# Controller.net
KiCad netlist of a schematic drawn in EAGLE
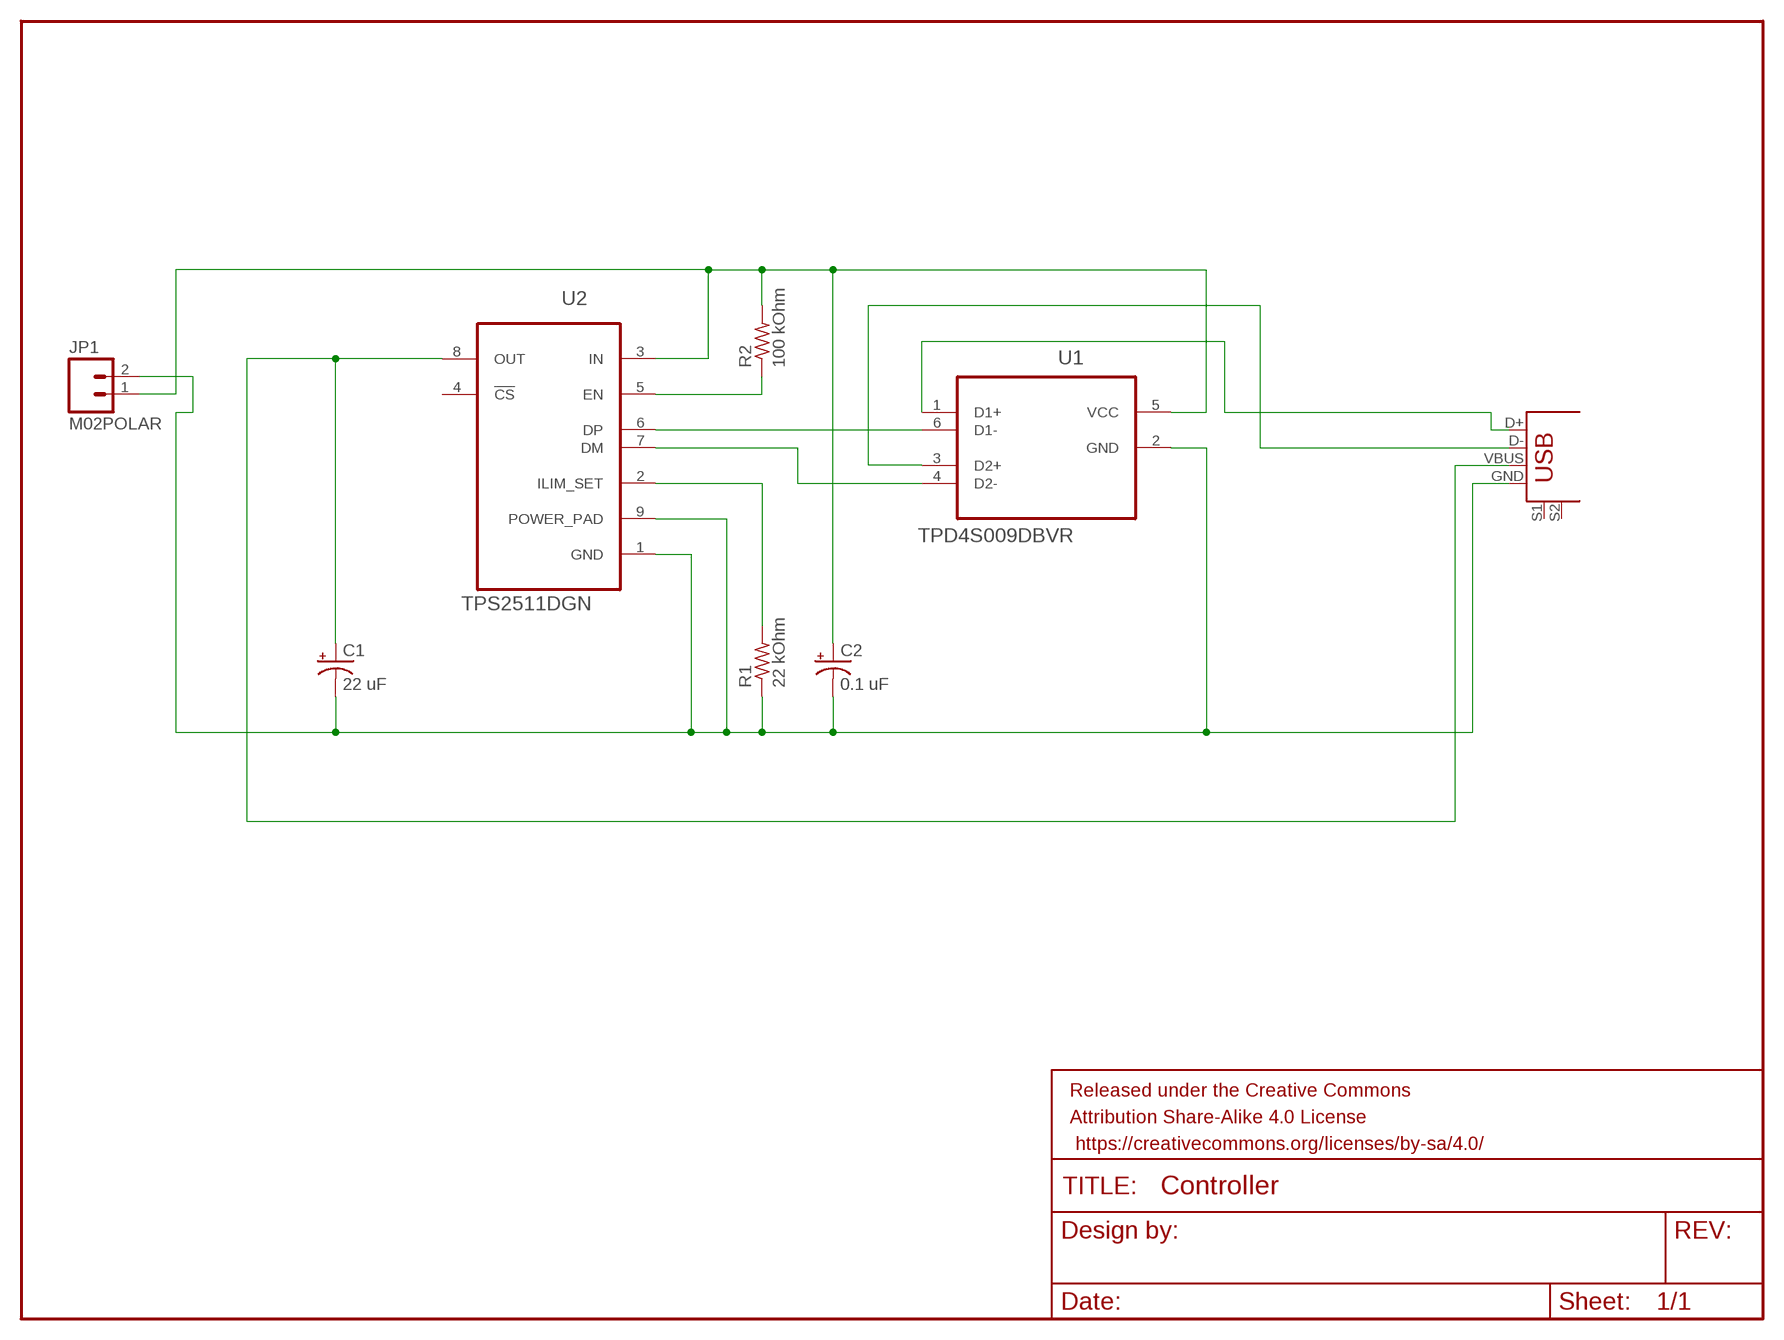
[diagram p0: schematic, sheet 1]

(export (version "E")
  (design (tool "Eeschema 10.0.6"))
  (components
    (comp (ref "C1")
      (value "22 uF")
      (footprint "eagle-import:E2,5-5")
      (libsource (lib "eagle-import") (part "CPOL-USE2.5-5"))
    )
    (comp (ref "C2")
      (value "0.1 uF")
      (footprint "eagle-import:E2,5-5")
      (libsource (lib "eagle-import") (part "CPOL-USE2.5-5"))
    )
    (comp (ref "FRAME1")
      (value "FRAME-LETTER")
      (footprint "eagle-import:CREATIVE_COMMONS")
      (libsource (lib "eagle-import") (part "FRAME-LETTER"))
    )
    (comp (ref "JP1")
      (value "M02POLAR")
      (footprint "eagle-import:MOLEX-1X2")
      (libsource (lib "eagle-import") (part "M02POLAR"))
    )
    (comp (ref "R1")
      (value "22 kOhm")
      (footprint "eagle-import:0207_10")
      (libsource (lib "eagle-import") (part "R-US_0207/10"))
    )
    (comp (ref "R2")
      (value "100 kOhm")
      (footprint "eagle-import:0207_10")
      (libsource (lib "eagle-import") (part "R-US_0207/10"))
    )
    (comp (ref "U$2")
      (value "USB+SHIELDUSB-A-S-NOSILK-FEMALE")
      (footprint "eagle-import:USB-A-S-NOSILK-FEMALE")
      (libsource (lib "eagle-import") (part "USB+SHIELDUSB-A-S-NOSILK-FEMALE"))
    )
    (comp (ref "U1")
      (value "TPD4S009DBVR")
      (footprint "eagle-import:SOT95P280X145-6N")
      (libsource (lib "eagle-import") (part "TPD4S009DBVR"))
    )
    (comp (ref "U2")
      (value "TPS2511DGN")
      (footprint "eagle-import:SOP65P490X110-9N")
      (fields (field (name "MPN") "TPS2511DGN "))
      (libsource (lib "eagle-import") (part "TPS2511DGN"))
    )
  )
  (nets
    (net (code "1") (name "Net-(U1-D1+)") (class "Default")
      (node (ref "U$2") (pin "D+") (pinfunction "D+_D+") (pintype "bidirectional"))
      (node (ref "U1") (pin "1") (pinfunction "D1+_1") (pintype "input"))
    )
    (net (code "2") (name "Net-(U1-D1-)") (class "Default")
      (node (ref "U1") (pin "6") (pinfunction "D1-_6") (pintype "input"))
      (node (ref "U2") (pin "6") (pinfunction "DP_6") (pintype "bidirectional"))
    )
    (net (code "3") (name "Net-(U1-D2+)") (class "Default")
      (node (ref "U$2") (pin "D-") (pinfunction "D-_D-") (pintype "bidirectional"))
      (node (ref "U1") (pin "3") (pinfunction "D2+_3") (pintype "input"))
    )
    (net (code "4") (name "Net-(U1-D2-)") (class "Default")
      (node (ref "U1") (pin "4") (pinfunction "D2-_4") (pintype "input"))
      (node (ref "U2") (pin "7") (pinfunction "DM_7") (pintype "bidirectional"))
    )
    (net (code "5") (name "Net-(U1-GND)") (class "Default")
      (node (ref "C1") (pin "-") (pinfunction "-_-") (pintype "passive"))
      (node (ref "C2") (pin "-") (pinfunction "-_-") (pintype "passive"))
      (node (ref "JP1") (pin "2") (pinfunction "2_2") (pintype "passive"))
      (node (ref "R1") (pin "1") (pinfunction "1_1") (pintype "passive"))
      (node (ref "U$2") (pin "GND") (pinfunction "GND_GND") (pintype "bidirectional"))
      (node (ref "U1") (pin "2") (pinfunction "GND_2") (pintype "passive"))
      (node (ref "U2") (pin "1") (pinfunction "GND_1") (pintype "passive"))
      (node (ref "U2") (pin "9") (pinfunction "POWER_PAD_9") (pintype "passive"))
    )
    (net (code "6") (name "Net-(U1-VCC)") (class "Default")
      (node (ref "C2") (pin "+") (pinfunction "+_+") (pintype "passive"))
      (node (ref "JP1") (pin "1") (pinfunction "1_1") (pintype "passive"))
      (node (ref "R2") (pin "2") (pinfunction "2_2") (pintype "passive"))
      (node (ref "U1") (pin "5") (pinfunction "VCC_5") (pintype "power_in"))
      (node (ref "U2") (pin "3") (pinfunction "IN_3") (pintype "power_in"))
    )
    (net (code "7") (name "Net-(U2-EN)") (class "Default")
      (node (ref "R2") (pin "1") (pinfunction "1_1") (pintype "passive"))
      (node (ref "U2") (pin "5") (pinfunction "EN_5") (pintype "input"))
    )
    (net (code "8") (name "Net-(U2-ILIM_SET)") (class "Default")
      (node (ref "R1") (pin "2") (pinfunction "2_2") (pintype "passive"))
      (node (ref "U2") (pin "2") (pinfunction "ILIM_SET_2") (pintype "input"))
    )
    (net (code "9") (name "Net-(U2-OUT)") (class "Default")
      (node (ref "C1") (pin "+") (pinfunction "+_+") (pintype "passive"))
      (node (ref "U$2") (pin "VBUS") (pinfunction "VBUS_VBUS") (pintype "bidirectional"))
      (node (ref "U2") (pin "8") (pinfunction "OUT_8") (pintype "output"))
    )
    (net (code "10") (name "unconnected-(U$2-PadS1)") (class "Default")
      (node (ref "U$2") (pin "S1") (pinfunction "S1_S1") (pintype "bidirectional"))
    )
    (net (code "11") (name "unconnected-(U$2-PadS2)") (class "Default")
      (node (ref "U$2") (pin "S2") (pinfunction "S2_S2") (pintype "bidirectional"))
    )
    (net (code "12") (name "unconnected-(U2-~{CS}-Pad4)") (class "Default")
      (node (ref "U2") (pin "4") (pinfunction "~{CS}_4") (pintype "output"))
    )
  )
)
